# SimPL_IMU_v1_0.net
KiCad netlist of a schematic drawn in Altium Designer
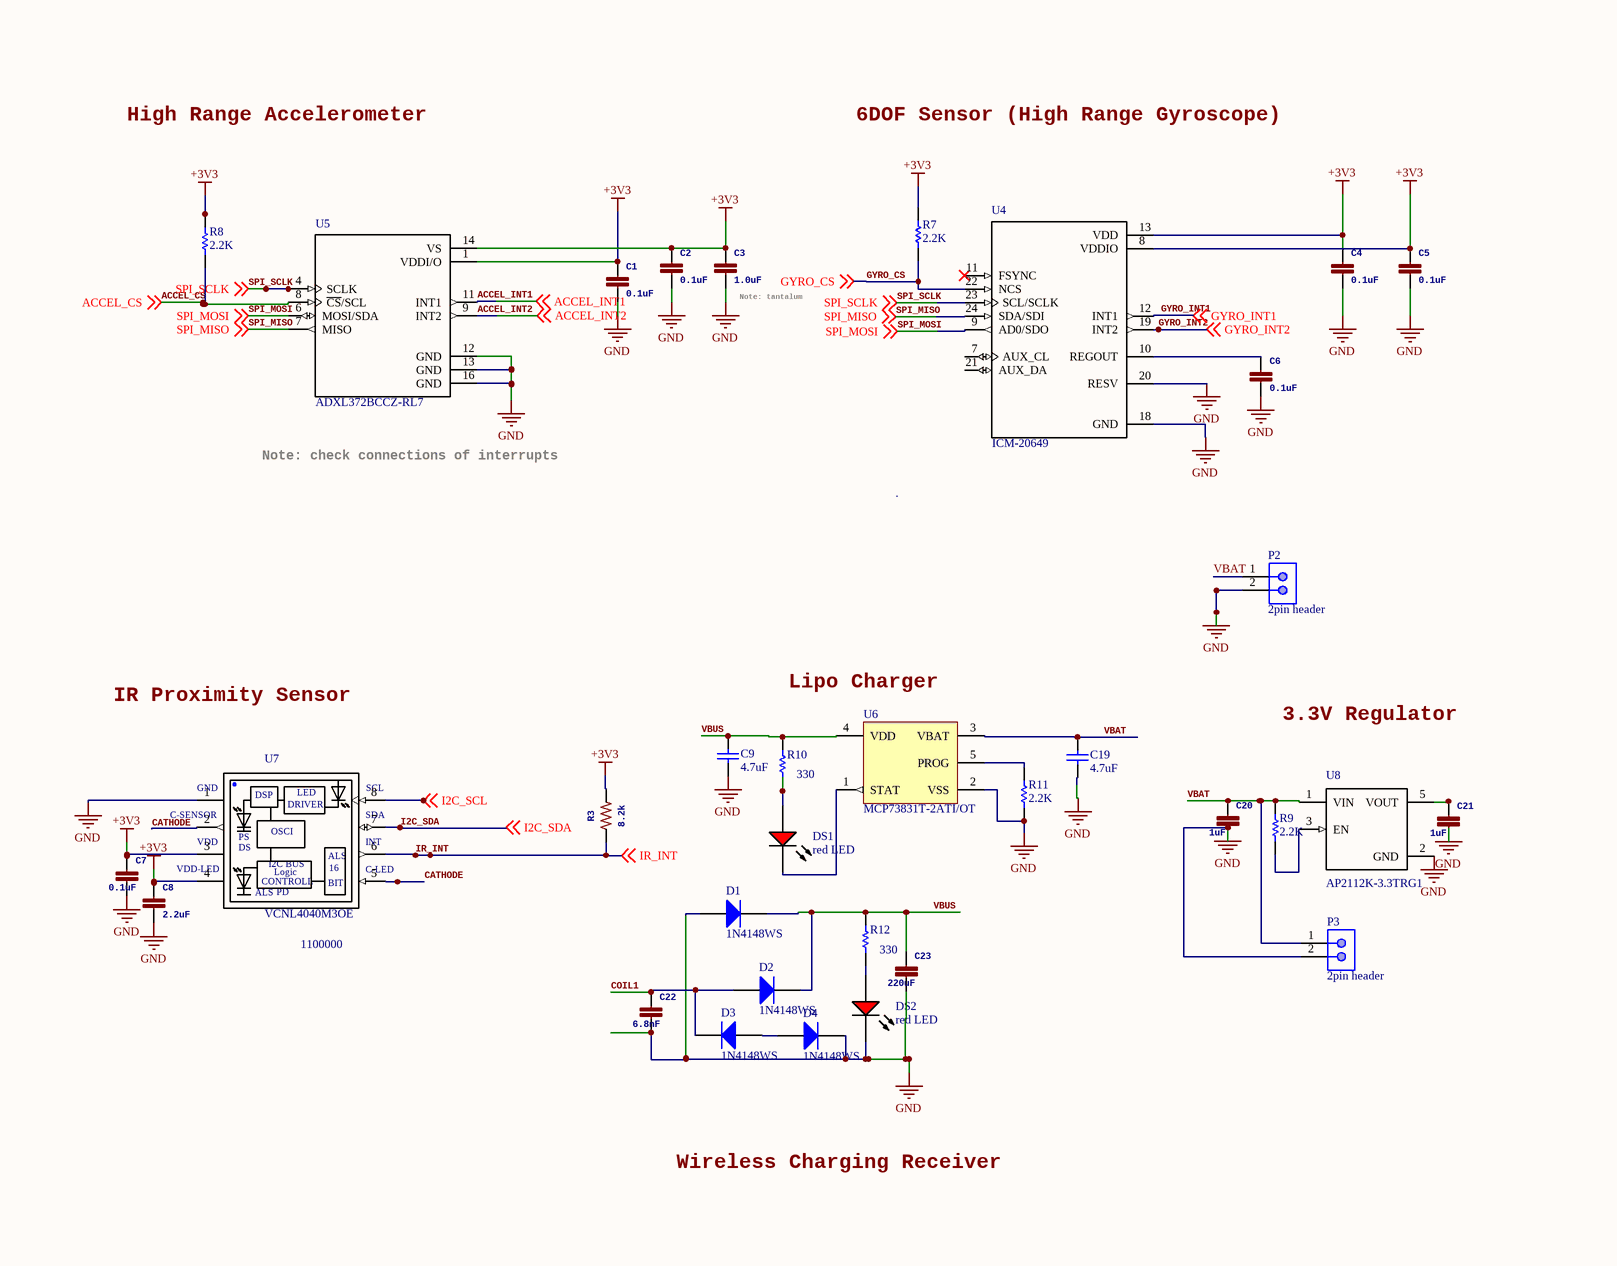
[diagram p0: SimPL_IMU_v1_0.SchDoc]

(export (version "E")
  (design (tool "Eeschema 10.0.6"))
  (components
    (comp (ref "C1")
      (value "0.1uF")
      (footprint "0402")
      (libsource (lib "SparkFun-Capacitors") (part "0.1UF-0402-16V-10%"))
    )
    (comp (ref "C2")
      (value "0.1uF")
      (footprint "0402")
      (libsource (lib "SparkFun-Capacitors") (part "0.1UF-0402-16V-10%"))
    )
    (comp (ref "C3")
      (value "1.0uF")
      (footprint "0402")
      (libsource (lib "SparkFun-Capacitors") (part "1.0UF-0402-16V-10%"))
    )
    (comp (ref "C4")
      (value "0.1uF")
      (footprint "0402")
      (libsource (lib "SparkFun-Capacitors") (part "0.1UF-0402-16V-10%"))
    )
    (comp (ref "C5")
      (value "0.1uF")
      (footprint "0402")
      (libsource (lib "SparkFun-Capacitors") (part "0.1UF-0402-16V-10%"))
    )
    (comp (ref "C6")
      (value "0.1uF")
      (footprint "0402")
      (libsource (lib "SparkFun-Capacitors") (part "0.1UF-0402-16V-10%"))
    )
    (comp (ref "C7")
      (value "0.1uF")
      (footprint "0402")
      (libsource (lib "SparkFun-Capacitors") (part "0.1UF-0402-16V-10%"))
    )
    (comp (ref "C8")
      (value "2.2uF")
      (footprint "0402")
      (libsource (lib "SparkFun-Capacitors") (part "0.1UF-0402-16V-10%"))
    )
    (comp (ref "C9")
      (value "4.7uF")
      (footprint "CAPC1005X65X10ML15")
      (description "Chip Capacitor, 4.7 uF, +/- 20%, 10 V, -55 to 85 degC, 0402 (1005 Metric), RoHS, Tape and Reel")
      (fields
        (field (name "TOLERANCE") "±20%")
        (field (name "PCN PART NUMBER") "MLCCPartNumberChange30/Nov/2012")
      )
      (libsource (lib "Altium Content Vault") (part "CAP-NP-2"))
    )
    (comp (ref "C19")
      (value "4.7uF")
      (footprint "CAPC1005X65X10ML15")
      (description "Chip Capacitor, 4.7 uF, +/- 20%, 10 V, -55 to 85 degC, 0402 (1005 Metric), RoHS, Tape and Reel")
      (fields
        (field (name "TOLERANCE") "±20%")
        (field (name "PCN PART NUMBER") "MLCCPartNumberChange30/Nov/2012")
      )
      (libsource (lib "Altium Content Vault") (part "CAP-NP-2"))
    )
    (comp (ref "C20")
      (value "1uF")
      (footprint "0402")
      (libsource (lib "SparkFun-Capacitors") (part "0.1UF-0402-16V-10%"))
    )
    (comp (ref "C21")
      (value "1uF")
      (footprint "0402")
      (libsource (lib "SparkFun-Capacitors") (part "0.1UF-0402-16V-10%"))
    )
    (comp (ref "C22")
      (value "6.8nF")
      (footprint "0402")
      (libsource (lib "SparkFun-Capacitors") (part "0.1UF-0402-16V-10%"))
    )
    (comp (ref "C23")
      (value "220uF")
      (footprint "0402")
      (libsource (lib "SparkFun-Capacitors") (part "0.1UF-0402-16V-10%"))
    )
    (comp (ref "D1")
      (value "1N4148WS")
      (footprint "DIOD-SOD323-2-A_V")
      (description "Fast Switching Diode, 75 V, 0.3 A, -65 to 150 degC, 2-Pin SOD323, RoHS, Tape and Reel")
      (libsource (lib "Altium Content Vault") (part "D-AK-2"))
    )
    (comp (ref "D2")
      (value "1N4148WS")
      (footprint "DIOD-SOD323-2-A_V")
      (description "Fast Switching Diode, 75 V, 0.3 A, -65 to 150 degC, 2-Pin SOD323, RoHS, Tape and Reel")
      (libsource (lib "Altium Content Vault") (part "D-AK-2"))
    )
    (comp (ref "D3")
      (value "1N4148WS")
      (footprint "DIOD-SOD323-2-A_V")
      (description "Fast Switching Diode, 75 V, 0.3 A, -65 to 150 degC, 2-Pin SOD323, RoHS, Tape and Reel")
      (libsource (lib "Altium Content Vault") (part "D-AK-2"))
    )
    (comp (ref "D4")
      (value "1N4148WS")
      (footprint "DIOD-SOD323-2-A_V")
      (description "Fast Switching Diode, 75 V, 0.3 A, -65 to 150 degC, 2-Pin SOD323, RoHS, Tape and Reel")
      (libsource (lib "Altium Content Vault") (part "D-AK-2"))
    )
    (comp (ref "DS1")
      (value "red LED")
      (footprint "VISH-TLMS1000_V")
      (description "Low Current LED, 40 mW, 1.8 V, -40 to 100 degC, 2-Pin SMD (0603), RoHS, Tape and Reel")
      (fields (field (name "MANUFACTURER") "Vishay"))
      (libsource (lib "Altium Content Vault") (part "LED-RED-AK-2"))
    )
    (comp (ref "DS2")
      (value "red LED")
      (footprint "VISH-TLMS1000_V")
      (description "Low Current LED, 40 mW, 1.8 V, -40 to 100 degC, 2-Pin SMD (0603), RoHS, Tape and Reel")
      (fields (field (name "MANUFACTURER") "Vishay"))
      (libsource (lib "Altium Content Vault") (part "LED-RED-AK-2"))
    )
    (comp (ref "P2")
      (value "2pin header")
      (footprint "AMPH-68000-102HLF_V")
      (description "Male Header, Pitch 2.54 mm, 1 x 2 Position, Height 8.38 mm, Tail Length 2.41 mm, RoHS, Bulk")
      (fields (field (name "MANUFACTURER") "FCI"))
      (libsource (lib "Altium Content Vault") (part "CN-1P-M-R2"))
    )
    (comp (ref "P3")
      (value "2pin header")
      (footprint "AMPH-68000-102HLF_V")
      (description "Male Header, Pitch 2.54 mm, 1 x 2 Position, Height 8.38 mm, Tail Length 2.41 mm, RoHS, Bulk")
      (fields (field (name "MANUFACTURER") "FCI"))
      (libsource (lib "Altium Content Vault") (part "CN-1P-M-R2"))
    )
    (comp (ref "R3")
      (value "8.2k")
      (footprint "0603")
      (libsource (lib "SparkFun-Resistors") (part "8.2KOHM-0603-1/10W-5%"))
    )
    (comp (ref "R7")
      (value "2.2K")
      (footprint "RESC1005X40X25ML10T10")
      (fields (field (name "PART NUMBER") "MC00625W040212K2") (field (name "MANUFACTURER") "Multicomp"))
      (libsource (lib "Altium Content Vault") (part "RES"))
    )
    (comp (ref "R8")
      (value "2.2K")
      (footprint "RESC1005X40X25ML10T10")
      (fields (field (name "PART NUMBER") "MC00625W040212K2") (field (name "MANUFACTURER") "Multicomp"))
      (libsource (lib "Altium Content Vault") (part "RES"))
    )
    (comp (ref "R9")
      (value "2.2K")
      (footprint "RESC1005X40X25ML10T10")
      (fields (field (name "PART NUMBER") "MC00625W040212K2") (field (name "MANUFACTURER") "Multicomp"))
      (libsource (lib "Altium Content Vault") (part "RES"))
    )
    (comp (ref "R10")
      (value "330")
      (footprint "RESC2013X50X30NL20T20")
      (fields (field (name "MANUFACTURER") "Vishay Dale") (field (name "PART NUMBER") "CRCW0805330RFKEA"))
      (libsource (lib "Altium Content Vault") (part "RES"))
    )
    (comp (ref "R11")
      (value "2.2K")
      (footprint "RESC1005X40X25ML10T10")
      (fields (field (name "PART NUMBER") "MC00625W040212K2") (field (name "MANUFACTURER") "Multicomp"))
      (libsource (lib "Altium Content Vault") (part "RES"))
    )
    (comp (ref "R12")
      (value "330")
      (footprint "RESC2013X50X30NL20T20")
      (fields (field (name "MANUFACTURER") "Vishay Dale") (field (name "PART NUMBER") "CRCW0805330RFKEA"))
      (libsource (lib "Altium Content Vault") (part "RES"))
    )
    (comp (ref "U4")
      (value "ICM-20649")
      (footprint "*QFN40P300X300X95-24N")
      (description "Wide-Range 6-Axis MEMS MotionTracking Device for Sports and High Impact Applications")
      (fields (field (name "MF") "TDK InvenSense"))
      (libsource (lib "ICM-20649") (part "ICM-20649"))
    )
    (comp (ref "U5")
      (value "ADXL372BCCZ-RL7")
      (footprint "*PQFN50P322X300X114-16N")
      (description "Accelerometer Triple Â±200g 2.5V 16-Pin LGA T/R")
      (fields (field (name "MF") "Analog Devices"))
      (libsource (lib "ADXL372BCCZ-RL7") (part "ADXL372BCCZ-RL7"))
    )
    (comp (ref "U6")
      (value "MCP73831T-2ATI/OT")
      (footprint "SOT-23-OT5_M")
      (libsource (lib "Altium Content Vault") (part "PM-BM-MCP73831-SOT5"))
    )
    (comp (ref "U7")
      (value "VCNL4040M3OE")
      (footprint "*VISHAY_VCNL4040_4X2X1.1")
      (description "VCNL4040 Series 3.6 V 200 mm 16 Bit I2C SMT Proximity and Ambient Light Sensor")
      (fields (field (name "MF") "Vishay"))
      (libsource (lib "VCNL4040M3OE") (part "VCNL4040M3OE"))
    )
    (comp (ref "U8")
      (value "AP2112K-3.3TRG1")
      (footprint "*SOT95P285X140-5N")
      (description "AP2112 Series 0.6 A 3.3 V Fixed Output SMT LDO Linear Regulator - SOT23-5")
      (fields (field (name "MF") "Diodes Inc."))
      (libsource (lib "AP2112K-3.3TRG1") (part "AP2112K-3.3TRG1"))
    )
  )
  (nets
    (net (code "1") (name "+3V3") (class "Default")
      (node (ref "C1") (pin "1") (pinfunction "1_1") (pintype "passive"))
      (node (ref "C2") (pin "1") (pinfunction "1_1") (pintype "passive"))
      (node (ref "C3") (pin "1") (pinfunction "1_1") (pintype "passive"))
      (node (ref "C4") (pin "1") (pinfunction "1_1") (pintype "passive"))
      (node (ref "C5") (pin "1") (pinfunction "1_1") (pintype "passive"))
      (node (ref "C7") (pin "1") (pinfunction "1_1") (pintype "passive"))
      (node (ref "C8") (pin "1") (pinfunction "1_1") (pintype "passive"))
      (node (ref "R3") (pin "2") (pinfunction "2_2") (pintype "passive"))
      (node (ref "R7") (pin "2") (pinfunction "2_2") (pintype "passive"))
      (node (ref "R8") (pin "2") (pinfunction "2_2") (pintype "passive"))
      (node (ref "U4") (pin "13") (pinfunction "VDD_13") (pintype "power_in"))
      (node (ref "U4") (pin "8") (pinfunction "VDDIO_8") (pintype "power_in"))
      (node (ref "U5") (pin "1") (pinfunction "VDDI/O_1") (pintype "power_in"))
      (node (ref "U5") (pin "14") (pinfunction "VS_14") (pintype "power_in"))
      (node (ref "U7") (pin "3") (pinfunction "VDD_3") (pintype "power_in"))
      (node (ref "U7") (pin "4") (pinfunction "VDD-LED_4") (pintype "power_in"))
    )
    (net (code "2") (name "/CATHODE") (class "Default")
      (node (ref "U7") (pin "2") (pinfunction "C-SENSOR_2") (pintype "output"))
      (node (ref "U7") (pin "5") (pinfunction "C-LED_5") (pintype "input"))
    )
    (net (code "3") (name "/COIL1") (class "Default")
      (node (ref "C22") (pin "1") (pinfunction "1_1") (pintype "passive"))
      (node (ref "D2") (pin "1") (pinfunction "A_1") (pintype "passive"))
      (node (ref "D3") (pin "2") (pinfunction "K_2") (pintype "passive"))
    )
    (net (code "4") (name "/VBAT") (class "Default")
      (node (ref "C19") (pin "2") (pinfunction "2_2") (pintype "passive"))
      (node (ref "C20") (pin "1") (pinfunction "1_1") (pintype "passive"))
      (node (ref "P2") (pin "1") (pinfunction "1_1") (pintype "passive"))
      (node (ref "P3") (pin "1") (pinfunction "1_1") (pintype "passive"))
      (node (ref "R9") (pin "2") (pinfunction "2_2") (pintype "passive"))
      (node (ref "U6") (pin "3") (pinfunction "VBAT_3") (pintype "power_in"))
      (node (ref "U8") (pin "1") (pinfunction "VIN_1") (pintype "power_in"))
    )
    (net (code "5") (name "/VBUS") (class "Default")
      (node (ref "C23") (pin "1") (pinfunction "1_1") (pintype "passive"))
      (node (ref "C9") (pin "2") (pinfunction "2_2") (pintype "passive"))
      (node (ref "D1") (pin "2") (pinfunction "K_2") (pintype "passive"))
      (node (ref "D2") (pin "2") (pinfunction "K_2") (pintype "passive"))
      (node (ref "R10") (pin "2") (pinfunction "2_2") (pintype "passive"))
      (node (ref "R12") (pin "2") (pinfunction "2_2") (pintype "passive"))
      (node (ref "U6") (pin "4") (pinfunction "VDD_4") (pintype "power_in"))
    )
    (net (code "6") (name "ACCEL_CS") (class "Default")
      (node (ref "R8") (pin "1") (pinfunction "1_1") (pintype "passive"))
      (node (ref "U5") (pin "8") (pinfunction "~{CS}/SCL_8") (pintype "input"))
    )
    (net (code "7") (name "ACCEL_INT1") (class "Default")
      (node (ref "U5") (pin "11") (pinfunction "INT1_11") (pintype "output"))
    )
    (net (code "8") (name "ACCEL_INT2") (class "Default")
      (node (ref "U5") (pin "9") (pinfunction "INT2_9") (pintype "output"))
    )
    (net (code "9") (name "GND") (class "Default")
      (node (ref "C1") (pin "2") (pinfunction "2_2") (pintype "passive"))
      (node (ref "C19") (pin "1") (pinfunction "1_1") (pintype "passive"))
      (node (ref "C2") (pin "2") (pinfunction "2_2") (pintype "passive"))
      (node (ref "C20") (pin "2") (pinfunction "2_2") (pintype "passive"))
      (node (ref "C21") (pin "2") (pinfunction "2_2") (pintype "passive"))
      (node (ref "C22") (pin "2") (pinfunction "2_2") (pintype "passive"))
      (node (ref "C23") (pin "2") (pinfunction "2_2") (pintype "passive"))
      (node (ref "C3") (pin "2") (pinfunction "2_2") (pintype "passive"))
      (node (ref "C4") (pin "2") (pinfunction "2_2") (pintype "passive"))
      (node (ref "C5") (pin "2") (pinfunction "2_2") (pintype "passive"))
      (node (ref "C6") (pin "2") (pinfunction "2_2") (pintype "passive"))
      (node (ref "C7") (pin "2") (pinfunction "2_2") (pintype "passive"))
      (node (ref "C8") (pin "2") (pinfunction "2_2") (pintype "passive"))
      (node (ref "C9") (pin "1") (pinfunction "1_1") (pintype "passive"))
      (node (ref "D1") (pin "1") (pinfunction "A_1") (pintype "passive"))
      (node (ref "D4") (pin "2") (pinfunction "K_2") (pintype "passive"))
      (node (ref "DS2") (pin "2") (pinfunction "K_2") (pintype "passive"))
      (node (ref "P2") (pin "2") (pinfunction "2_2") (pintype "passive"))
      (node (ref "P3") (pin "2") (pinfunction "2_2") (pintype "passive"))
      (node (ref "R11") (pin "1") (pinfunction "1_1") (pintype "passive"))
      (node (ref "U4") (pin "18") (pinfunction "GND_18") (pintype "power_in"))
      (node (ref "U4") (pin "20") (pinfunction "RESV_20") (pintype "passive"))
      (node (ref "U5") (pin "12") (pinfunction "GND_12") (pintype "power_in"))
      (node (ref "U5") (pin "13") (pinfunction "GND_13") (pintype "power_in"))
      (node (ref "U5") (pin "16") (pinfunction "GND_16") (pintype "power_in"))
      (node (ref "U6") (pin "2") (pinfunction "VSS_2") (pintype "power_in"))
      (node (ref "U7") (pin "1") (pinfunction "GND_1") (pintype "power_in"))
      (node (ref "U8") (pin "2") (pinfunction "GND_2") (pintype "power_in"))
    )
    (net (code "10") (name "GYRO_CS") (class "Default")
      (node (ref "R7") (pin "1") (pinfunction "1_1") (pintype "passive"))
      (node (ref "U4") (pin "22") (pinfunction "NCS_22") (pintype "input"))
    )
    (net (code "11") (name "GYRO_INT1") (class "Default")
      (node (ref "U4") (pin "12") (pinfunction "INT1_12") (pintype "output"))
    )
    (net (code "12") (name "GYRO_INT2") (class "Default")
      (node (ref "U4") (pin "19") (pinfunction "INT2_19") (pintype "output"))
    )
    (net (code "13") (name "I2C_SCL") (class "Default")
      (node (ref "U7") (pin "8") (pinfunction "SCL_8") (pintype "input"))
    )
    (net (code "14") (name "I2C_SDA") (class "Default")
      (node (ref "U7") (pin "7") (pinfunction "SDA_7") (pintype "bidirectional"))
    )
    (net (code "15") (name "IR_INT") (class "Default")
      (node (ref "R3") (pin "1") (pinfunction "1_1") (pintype "passive"))
      (node (ref "U7") (pin "6") (pinfunction "INT_6") (pintype "output"))
    )
    (net (code "16") (name "Net-(D3-A)") (class "Default")
      (node (ref "D3") (pin "1") (pinfunction "A_1") (pintype "passive"))
      (node (ref "D4") (pin "1") (pinfunction "A_1") (pintype "passive"))
    )
    (net (code "17") (name "Net-(DS1-A)") (class "Default")
      (node (ref "DS1") (pin "1") (pinfunction "A_1") (pintype "passive"))
      (node (ref "R10") (pin "1") (pinfunction "1_1") (pintype "passive"))
    )
    (net (code "18") (name "Net-(DS1-K)") (class "Default")
      (node (ref "DS1") (pin "2") (pinfunction "K_2") (pintype "passive"))
      (node (ref "U6") (pin "1") (pinfunction "STAT_1") (pintype "output"))
    )
    (net (code "19") (name "Net-(DS2-A)") (class "Default")
      (node (ref "DS2") (pin "1") (pinfunction "A_1") (pintype "passive"))
      (node (ref "R12") (pin "1") (pinfunction "1_1") (pintype "passive"))
    )
    (net (code "20") (name "Net-(U4-REGOUT)") (class "Default")
      (node (ref "C6") (pin "1") (pinfunction "1_1") (pintype "passive"))
      (node (ref "U4") (pin "10") (pinfunction "REGOUT_10") (pintype "passive"))
    )
    (net (code "21") (name "Net-(U6-PROG)") (class "Default")
      (node (ref "R11") (pin "2") (pinfunction "2_2") (pintype "passive"))
      (node (ref "U6") (pin "5") (pinfunction "PROG_5") (pintype "passive"))
    )
    (net (code "22") (name "Net-(U8-EN)") (class "Default")
      (node (ref "R9") (pin "1") (pinfunction "1_1") (pintype "passive"))
      (node (ref "U8") (pin "3") (pinfunction "EN_3") (pintype "input"))
    )
    (net (code "23") (name "Net-(U8-VOUT)") (class "Default")
      (node (ref "C21") (pin "1") (pinfunction "1_1") (pintype "passive"))
      (node (ref "U8") (pin "5") (pinfunction "VOUT_5") (pintype "power_in"))
    )
    (net (code "24") (name "SPI_MISO") (class "Default")
      (node (ref "U4") (pin "24") (pinfunction "SDA/SDI_24") (pintype "input"))
      (node (ref "U5") (pin "7") (pinfunction "MISO_7") (pintype "output"))
    )
    (net (code "25") (name "SPI_MOSI") (class "Default")
      (node (ref "U4") (pin "9") (pinfunction "AD0/SDO_9") (pintype "output"))
      (node (ref "U5") (pin "6") (pinfunction "MOSI/SDA_6") (pintype "bidirectional"))
    )
    (net (code "26") (name "SPI_SCLK") (class "Default")
      (node (ref "U4") (pin "23") (pinfunction "SCL/SCLK_23") (pintype "input"))
      (node (ref "U5") (pin "4") (pinfunction "SCLK_4") (pintype "input"))
    )
    (net (code "27") (name "unconnected-(U4-AUX_CL-Pad7)") (class "Default")
      (node (ref "U4") (pin "7") (pinfunction "AUX_CL_7") (pintype "bidirectional"))
    )
    (net (code "28") (name "unconnected-(U4-AUX_DA-Pad21)") (class "Default")
      (node (ref "U4") (pin "21") (pinfunction "AUX_DA_21") (pintype "bidirectional"))
    )
    (net (code "29") (name "unconnected-(U4-FSYNC-Pad11)") (class "Default")
      (node (ref "U4") (pin "11") (pinfunction "FSYNC_11") (pintype "input+no_connect"))
    )
  )
)
